# Power.net
KiCad netlist of a schematic drawn in Altium Designer
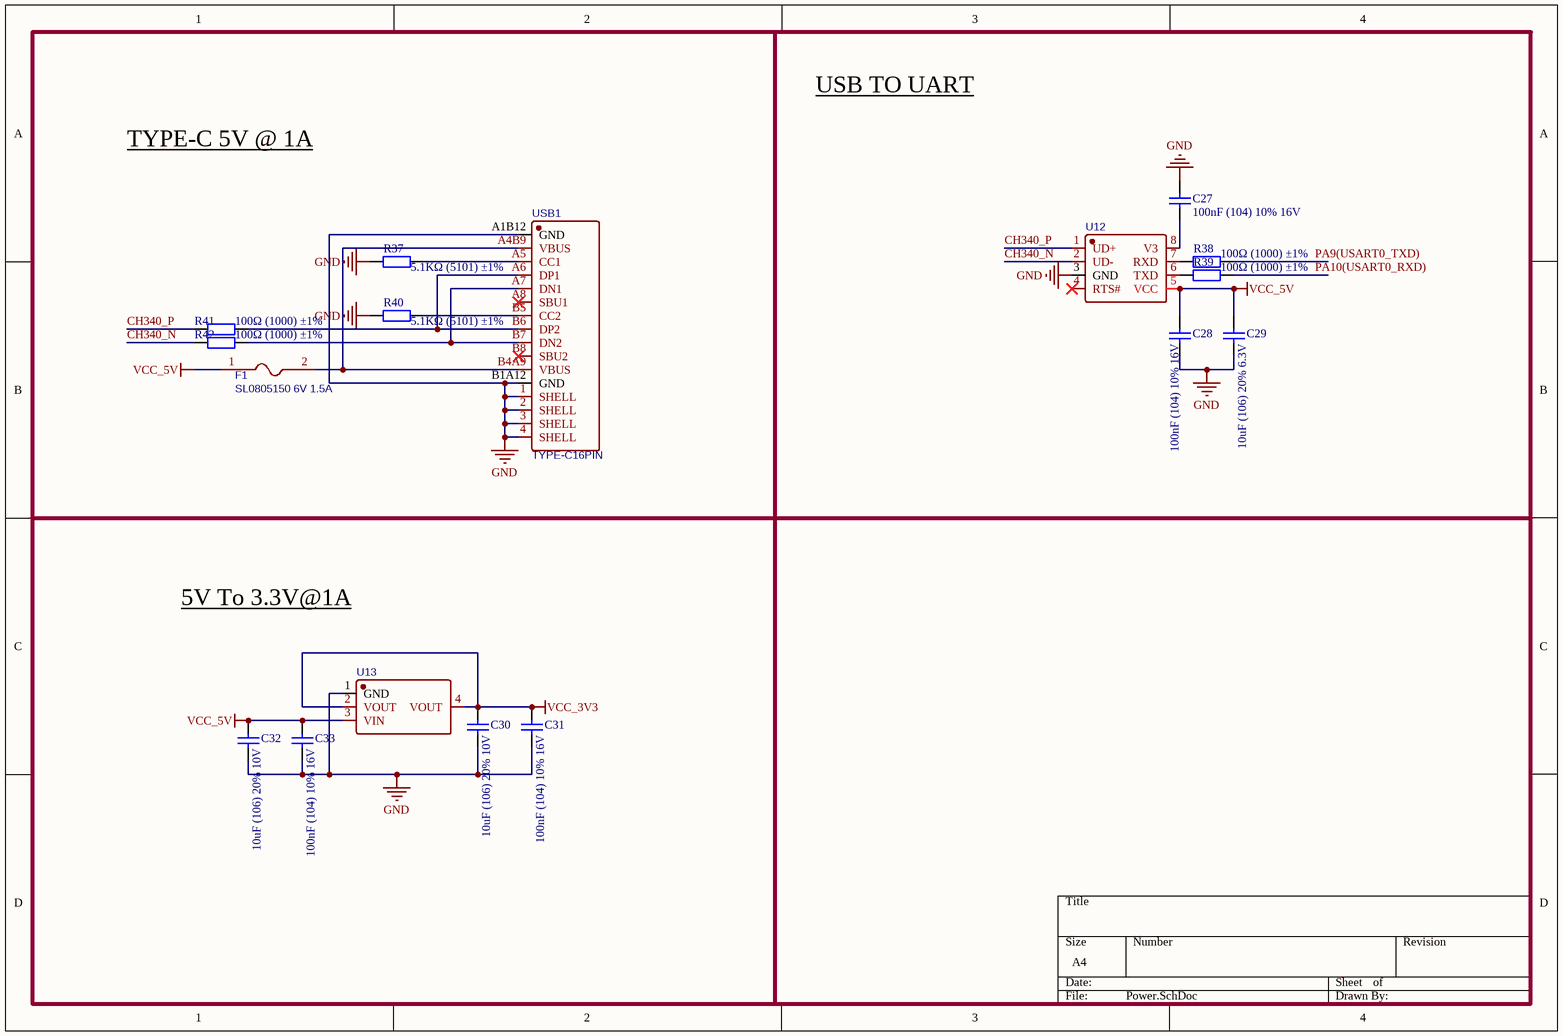
[diagram p0: Power.SchDoc]

(export (version "E")
  (design (tool "Eeschema 10.0.6"))
  (components
    (comp (ref "C27")
      (value "100nF (104) 10% 16V")
      (footprint "0402_C")
      (description "贴片电容")
      (libsource (lib "Miscellaneous Devices LC") (part "0402 100nF (104) 10% 16V"))
    )
    (comp (ref "C28")
      (value "100nF (104) 10% 16V")
      (footprint "0402_C")
      (description "贴片电容")
      (libsource (lib "Miscellaneous Devices LC") (part "0402 100nF (104) 10% 16V"))
    )
    (comp (ref "C29")
      (value "10uF (106) 20% 6.3V")
      (footprint "0402_C")
      (description "贴片电容")
      (libsource (lib "Miscellaneous Devices LC") (part "0402 10uF (106) 20% 6.3V"))
    )
    (comp (ref "C30")
      (value "10uF (106) 20% 10V")
      (footprint "0402_C")
      (description "贴片电容")
      (libsource (lib "Miscellaneous Devices LC") (part "0402 10uF (106) 20% 6.3V"))
    )
    (comp (ref "C31")
      (value "100nF (104) 10% 16V")
      (footprint "0402_C")
      (description "贴片电容")
      (libsource (lib "Miscellaneous Devices LC") (part "0402 100nF (104) 10% 16V"))
    )
    (comp (ref "C32")
      (value "10uF (106) 20% 10V")
      (footprint "0402_C")
      (description "贴片电容")
      (libsource (lib "Miscellaneous Devices LC") (part "0402 10uF (106) 20% 6.3V"))
    )
    (comp (ref "C33")
      (value "100nF (104) 10% 16V")
      (footprint "0402_C")
      (description "贴片电容")
      (libsource (lib "Miscellaneous Devices LC") (part "0402 100nF (104) 10% 16V"))
    )
    (comp (ref "F1")
      (value "SL0805150 6V 1.5A")
      (footprint "F0805")
      (fields (field (name "BOM_MANUFACTURER PART") "SL0805150") (field (name "BOM_SUPPLIER PART") "C70156"))
      (libsource (lib "医疗床PCB") (part "SL0805150"))
    )
    (comp (ref "R37")
      (value "5.1KΩ (5101) ±1%")
      (footprint "0402_R")
      (description "贴片电阻")
      (libsource (lib "Miscellaneous Devices LC") (part "0402 5.1KΩ (5101) 1%"))
    )
    (comp (ref "R38")
      (value "100Ω (1000) ±1%")
      (footprint "0402_R")
      (description "贴片电阻")
      (libsource (lib "Miscellaneous Devices LC") (part "0402 100Ω (1000) 1%"))
    )
    (comp (ref "R39")
      (value "100Ω (1000) ±1%")
      (footprint "0402_R")
      (description "贴片电阻")
      (libsource (lib "Miscellaneous Devices LC") (part "0402 100Ω (1000) 1%"))
    )
    (comp (ref "R40")
      (value "5.1KΩ (5101) ±1%")
      (footprint "0402_R")
      (description "贴片电阻")
      (libsource (lib "Miscellaneous Devices LC") (part "0402 5.1KΩ (5101) 1%"))
    )
    (comp (ref "R41")
      (value "100Ω (1000) ±1%")
      (footprint "0402_R")
      (description "贴片电阻")
      (libsource (lib "Miscellaneous Devices LC") (part "0402 100Ω (1000) 1%"))
    )
    (comp (ref "R42")
      (value "100Ω (1000) ±1%")
      (footprint "0402_R")
      (description "贴片电阻")
      (libsource (lib "Miscellaneous Devices LC") (part "0402 100Ω (1000) 1%"))
    )
    (comp (ref "U12")
      (value "~")
      (footprint "SOP-8_L5.0-W4.0-P1.27-LS6.0-BL")
      (fields
        (field (name "BOM_SUPPLIER PART") "C506813")
        (field (name "BOM_MANUFACTURER PART") "CH340N")
        (field (name "CONTRIBUTOR") "LCSC")
      )
      (libsource (lib "医疗床PCB") (part "CH340N"))
    )
    (comp (ref "U13")
      (value "~")
      (footprint "SOT-223-3_L6.5-W3.4-P2.30-LS7.0-BR")
      (fields
        (field (name "BOM_MANUFACTURER PART") "SC1117-3.3V")
        (field (name "BOM_SUPPLIER PART") "C173386")
        (field (name "CONTRIBUTOR") "LCSC")
      )
      (libsource (lib "医疗床PCB") (part "AMS1117-3.3V"))
    )
    (comp (ref "USB1")
      (value "TYPE-C16PIN")
      (footprint "USB-C-SMD_TYPE-C16PIN")
      (fields (field (name "BOM_SUPPLIER PART") "C393939") (field (name "CONTRIBUTOR") "LCSC"))
      (libsource (lib "医疗床PCB") (part "TYPE-C16PIN"))
    )
  )
  (nets
    (net (code "1") (name "/CH340_N") (class "Default")
      (node (ref "R42") (pin "1") (pinfunction "1_1") (pintype "passive"))
      (node (ref "U12") (pin "2") (pinfunction "UD-_2") (pintype "passive"))
    )
    (net (code "2") (name "/CH340_P") (class "Default")
      (node (ref "R41") (pin "1") (pinfunction "1_1") (pintype "passive"))
      (node (ref "U12") (pin "1") (pinfunction "UD+_1") (pintype "passive"))
    )
    (net (code "3") (name "/PA9(USART0_TXD)") (class "Default")
      (node (ref "R38") (pin "2") (pinfunction "2_2") (pintype "passive"))
    )
    (net (code "4") (name "/PA10(USART0_RXD)") (class "Default")
      (node (ref "R39") (pin "2") (pinfunction "2_2") (pintype "passive"))
    )
    (net (code "5") (name "GND") (class "Default")
      (node (ref "C27") (pin "2") (pinfunction "2_2") (pintype "passive"))
      (node (ref "C28") (pin "1") (pinfunction "1_1") (pintype "passive"))
      (node (ref "C29") (pin "1") (pinfunction "1_1") (pintype "passive"))
      (node (ref "C30") (pin "1") (pinfunction "1_1") (pintype "passive"))
      (node (ref "C31") (pin "1") (pinfunction "1_1") (pintype "passive"))
      (node (ref "C32") (pin "1") (pinfunction "1_1") (pintype "passive"))
      (node (ref "C33") (pin "1") (pinfunction "1_1") (pintype "passive"))
      (node (ref "R37") (pin "2") (pinfunction "2_2") (pintype "passive"))
      (node (ref "R40") (pin "2") (pinfunction "2_2") (pintype "passive"))
      (node (ref "U12") (pin "3") (pinfunction "GND_3") (pintype "passive"))
      (node (ref "U13") (pin "1") (pinfunction "GND_1") (pintype "passive"))
      (node (ref "USB1") (pin "1") (pinfunction "SHELL_1") (pintype "passive"))
      (node (ref "USB1") (pin "2") (pinfunction "SHELL_2") (pintype "passive"))
      (node (ref "USB1") (pin "3") (pinfunction "SHELL_3") (pintype "passive"))
      (node (ref "USB1") (pin "4") (pinfunction "SHELL_4") (pintype "passive"))
      (node (ref "USB1") (pin "A1B12") (pinfunction "GND_A1B12") (pintype "passive"))
      (node (ref "USB1") (pin "B1A12") (pinfunction "GND_B1A12") (pintype "passive"))
    )
    (net (code "6") (name "Net-(F1-Pad2)") (class "Default")
      (node (ref "F1") (pin "2") (pinfunction "2_2") (pintype "passive"))
      (node (ref "USB1") (pin "A4B9") (pinfunction "VBUS_A4B9") (pintype "passive"))
      (node (ref "USB1") (pin "B4A9") (pinfunction "VBUS_B4A9") (pintype "passive"))
    )
    (net (code "7") (name "Net-(U12-RXD)") (class "Default")
      (node (ref "R38") (pin "1") (pinfunction "1_1") (pintype "passive"))
      (node (ref "U12") (pin "7") (pinfunction "RXD_7") (pintype "passive"))
    )
    (net (code "8") (name "Net-(U12-TXD)") (class "Default")
      (node (ref "R39") (pin "1") (pinfunction "1_1") (pintype "passive"))
      (node (ref "U12") (pin "6") (pinfunction "TXD_6") (pintype "passive"))
    )
    (net (code "9") (name "Net-(U12-V3)") (class "Default")
      (node (ref "C27") (pin "1") (pinfunction "1_1") (pintype "passive"))
      (node (ref "U12") (pin "8") (pinfunction "V3_8") (pintype "passive"))
    )
    (net (code "10") (name "Net-(USB1-CC1)") (class "Default")
      (node (ref "R37") (pin "1") (pinfunction "1_1") (pintype "passive"))
      (node (ref "USB1") (pin "A5") (pinfunction "CC1_A5") (pintype "passive"))
    )
    (net (code "11") (name "Net-(USB1-CC2)") (class "Default")
      (node (ref "R40") (pin "1") (pinfunction "1_1") (pintype "passive"))
      (node (ref "USB1") (pin "B5") (pinfunction "CC2_B5") (pintype "passive"))
    )
    (net (code "12") (name "Net-(USB1-DN1)") (class "Default")
      (node (ref "R42") (pin "2") (pinfunction "2_2") (pintype "passive"))
      (node (ref "USB1") (pin "A7") (pinfunction "DN1_A7") (pintype "passive"))
      (node (ref "USB1") (pin "B7") (pinfunction "DN2_B7") (pintype "passive"))
    )
    (net (code "13") (name "Net-(USB1-DP1)") (class "Default")
      (node (ref "R41") (pin "2") (pinfunction "2_2") (pintype "passive"))
      (node (ref "USB1") (pin "A6") (pinfunction "DP1_A6") (pintype "passive"))
      (node (ref "USB1") (pin "B6") (pinfunction "DP2_B6") (pintype "passive"))
    )
    (net (code "14") (name "VCC_3V3") (class "Default")
      (node (ref "C30") (pin "2") (pinfunction "2_2") (pintype "passive"))
      (node (ref "C31") (pin "2") (pinfunction "2_2") (pintype "passive"))
      (node (ref "U13") (pin "2") (pinfunction "VOUT_2") (pintype "passive"))
      (node (ref "U13") (pin "4") (pinfunction "VOUT_4") (pintype "passive"))
    )
    (net (code "15") (name "VCC_5V") (class "Default")
      (node (ref "C28") (pin "2") (pinfunction "2_2") (pintype "passive"))
      (node (ref "C29") (pin "2") (pinfunction "2_2") (pintype "passive"))
      (node (ref "C32") (pin "2") (pinfunction "2_2") (pintype "passive"))
      (node (ref "C33") (pin "2") (pinfunction "2_2") (pintype "passive"))
      (node (ref "F1") (pin "1") (pinfunction "1_1") (pintype "passive"))
      (node (ref "U12") (pin "5") (pinfunction "VCC_5") (pintype "passive"))
      (node (ref "U13") (pin "3") (pinfunction "VIN_3") (pintype "passive"))
    )
    (net (code "16") (name "unconnected-(U12-RTS#-Pad4)") (class "Default")
      (node (ref "U12") (pin "4") (pinfunction "RTS#_4") (pintype "passive+no_connect"))
    )
    (net (code "17") (name "unconnected-(USB1-SBU1-PadA8)") (class "Default")
      (node (ref "USB1") (pin "A8") (pinfunction "SBU1_A8") (pintype "passive+no_connect"))
    )
    (net (code "18") (name "unconnected-(USB1-SBU2-PadB8)") (class "Default")
      (node (ref "USB1") (pin "B8") (pinfunction "SBU2_B8") (pintype "passive+no_connect"))
    )
  )
)
